# DAM10_Relays.net
KiCad netlist of a schematic drawn in Altium Designer
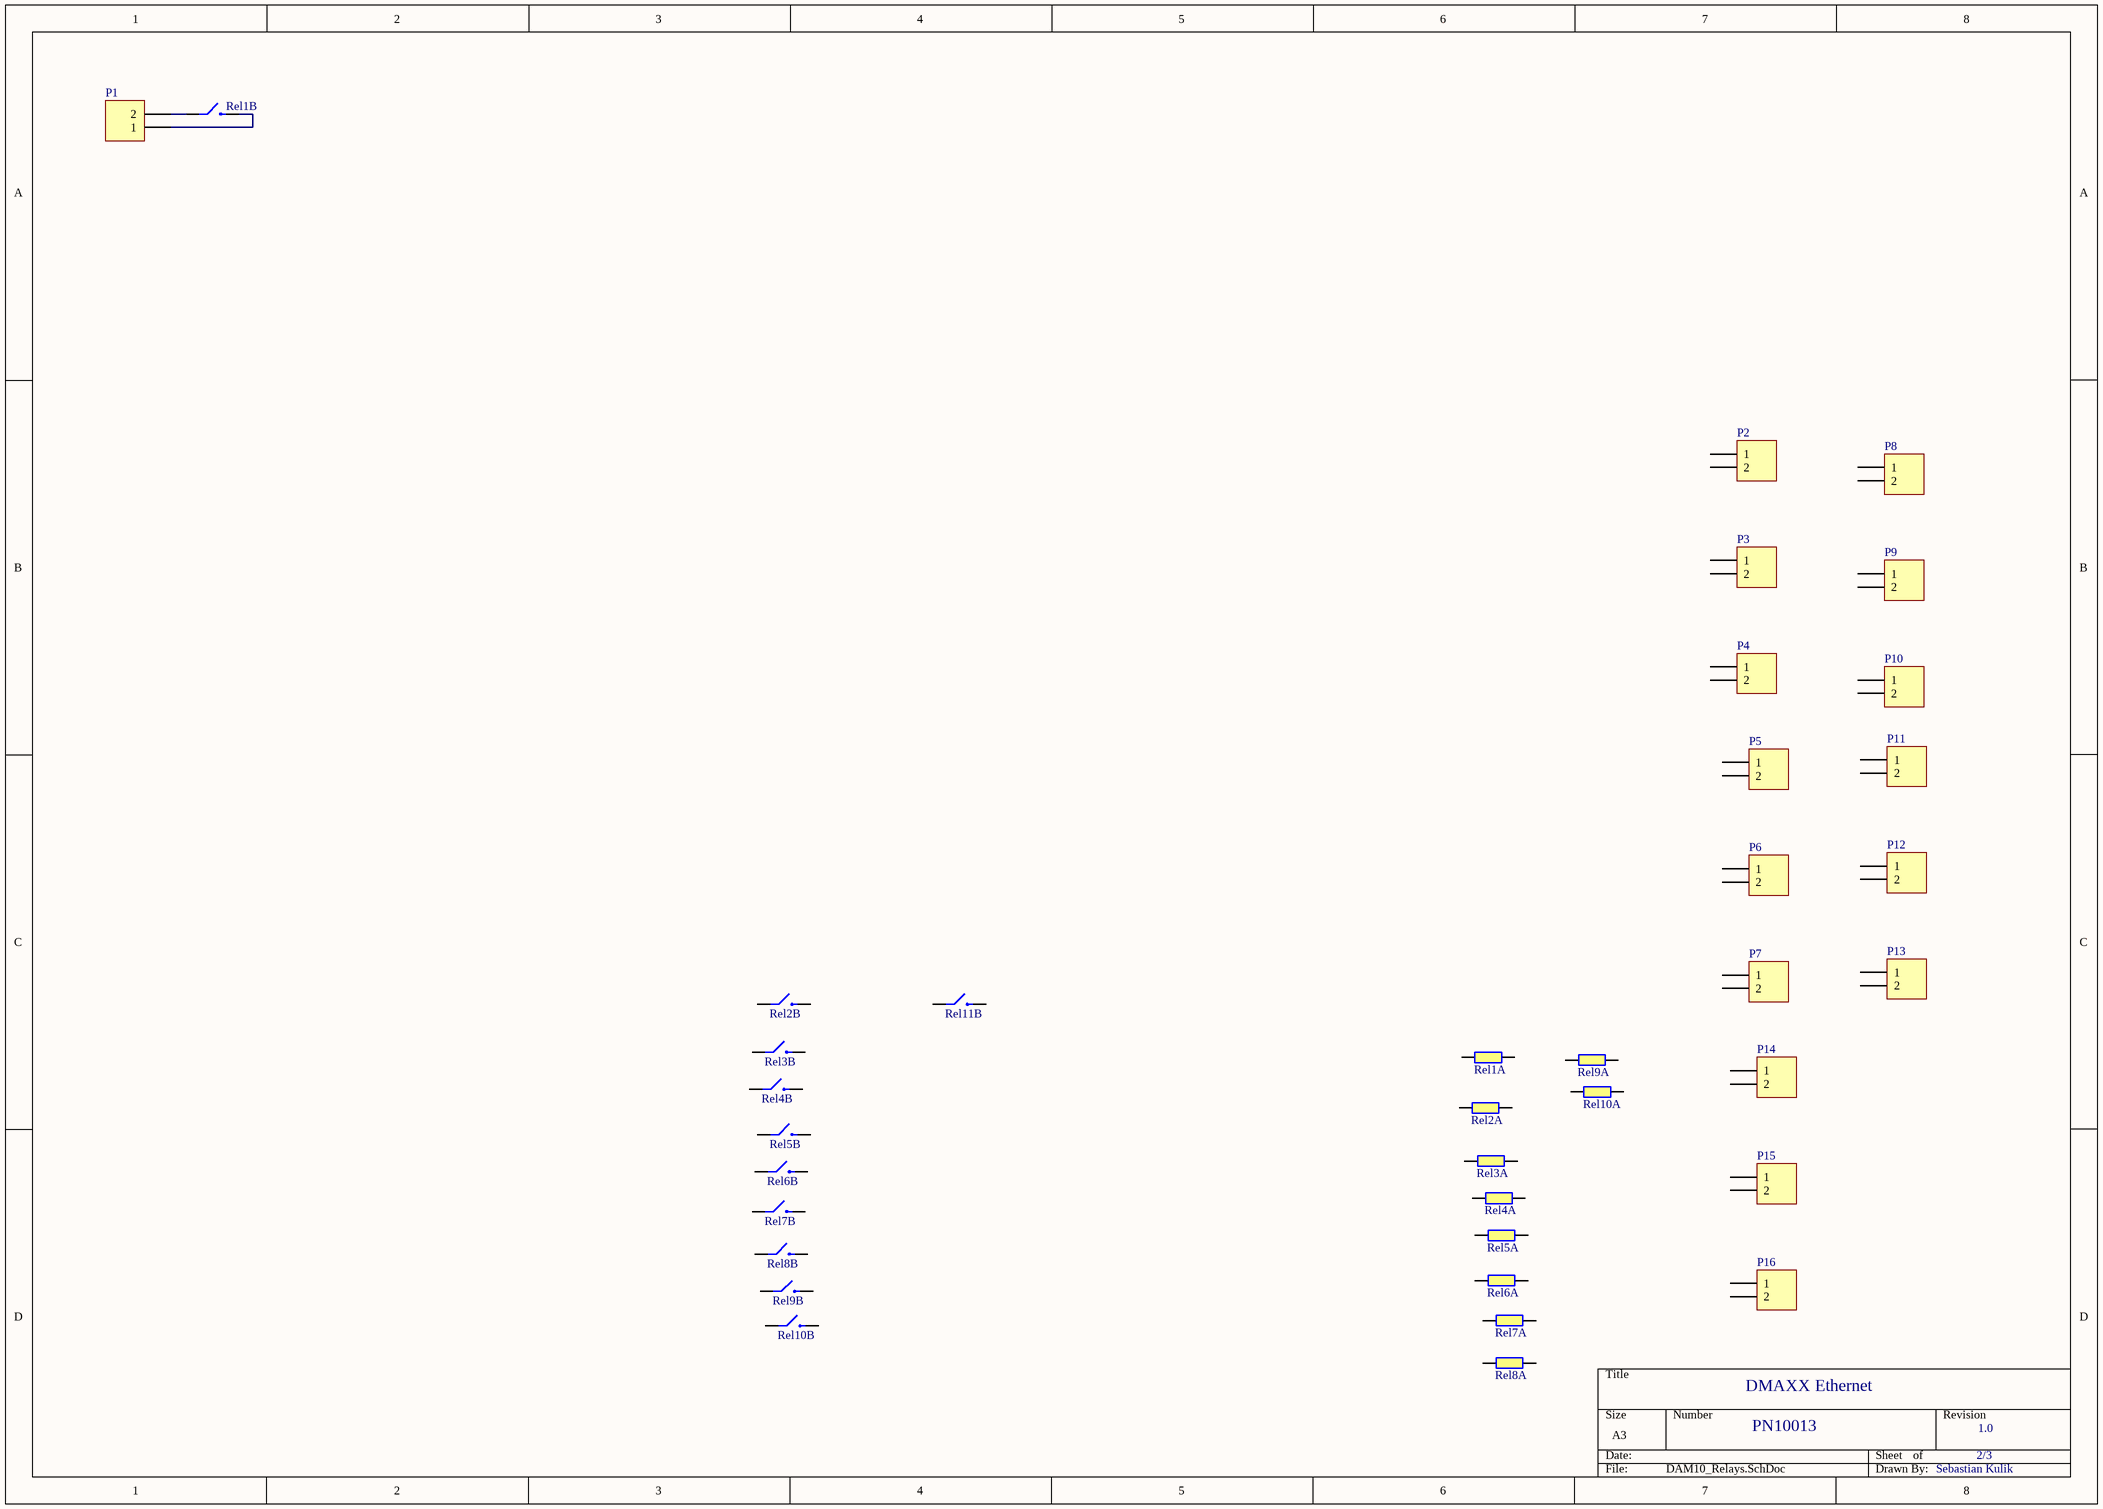
[diagram p0: DAM10_Relays.SchDoc]

(export (version "E")
  (design (tool "Eeschema 10.0.6"))
  (components
    (comp (ref "P1")
      (value "PHOENIX_1715721")
      (footprint "Phoenix-2-5_08")
      (description "Phoenix, 2 pol, 5.08mm, 22A, 715721")
      (fields (field (name "MANUFACTURER") "Phoenix") (field (name "PUBLISHER") "Sebastian Kulik"))
      (libsource (lib "") (part "2Pol_1715721_1"))
    )
    (comp (ref "P2")
      (value "PHOENIX_1715721")
      (footprint "Phoenix-2-5_08")
      (description "Phoenix, 2 pol, 5.08mm, 22A, 715721")
      (fields (field (name "MANUFACTURER") "Phoenix") (field (name "PUBLISHER") "Sebastian Kulik"))
      (libsource (lib "Connectors") (part "2Pol_1715721"))
    )
    (comp (ref "P3")
      (value "PHOENIX_1715721")
      (footprint "Phoenix-2-5_08")
      (description "Phoenix, 2 pol, 5.08mm, 22A, 715721")
      (fields (field (name "MANUFACTURER") "Phoenix") (field (name "PUBLISHER") "Sebastian Kulik"))
      (libsource (lib "Connectors") (part "2Pol_1715721"))
    )
    (comp (ref "P4")
      (value "PHOENIX_1715721")
      (footprint "Phoenix-2-5_08")
      (description "Phoenix, 2 pol, 5.08mm, 22A, 715721")
      (fields (field (name "MANUFACTURER") "Phoenix") (field (name "PUBLISHER") "Sebastian Kulik"))
      (libsource (lib "Connectors") (part "2Pol_1715721"))
    )
    (comp (ref "P5")
      (value "PHOENIX_1715721")
      (footprint "Phoenix-2-5_08")
      (description "Phoenix, 2 pol, 5.08mm, 22A, 715721")
      (fields (field (name "MANUFACTURER") "Phoenix") (field (name "PUBLISHER") "Sebastian Kulik"))
      (libsource (lib "Connectors") (part "2Pol_1715721"))
    )
    (comp (ref "P6")
      (value "PHOENIX_1715721")
      (footprint "Phoenix-2-5_08")
      (description "Phoenix, 2 pol, 5.08mm, 22A, 715721")
      (fields (field (name "MANUFACTURER") "Phoenix") (field (name "PUBLISHER") "Sebastian Kulik"))
      (libsource (lib "Connectors") (part "2Pol_1715721"))
    )
    (comp (ref "P7")
      (value "PHOENIX_1715721")
      (footprint "Phoenix-2-5_08")
      (description "Phoenix, 2 pol, 5.08mm, 22A, 715721")
      (fields (field (name "MANUFACTURER") "Phoenix") (field (name "PUBLISHER") "Sebastian Kulik"))
      (libsource (lib "Connectors") (part "2Pol_1715721"))
    )
    (comp (ref "P8")
      (value "PHOENIX_1715721")
      (footprint "Phoenix-2-5_08")
      (description "Phoenix, 2 pol, 5.08mm, 22A, 715721")
      (fields (field (name "MANUFACTURER") "Phoenix") (field (name "PUBLISHER") "Sebastian Kulik"))
      (libsource (lib "Connectors") (part "2Pol_1715721"))
    )
    (comp (ref "P9")
      (value "PHOENIX_1715721")
      (footprint "Phoenix-2-5_08")
      (description "Phoenix, 2 pol, 5.08mm, 22A, 715721")
      (fields (field (name "MANUFACTURER") "Phoenix") (field (name "PUBLISHER") "Sebastian Kulik"))
      (libsource (lib "Connectors") (part "2Pol_1715721"))
    )
    (comp (ref "P10")
      (value "PHOENIX_1715721")
      (footprint "Phoenix-2-5_08")
      (description "Phoenix, 2 pol, 5.08mm, 22A, 715721")
      (fields (field (name "MANUFACTURER") "Phoenix") (field (name "PUBLISHER") "Sebastian Kulik"))
      (libsource (lib "Connectors") (part "2Pol_1715721"))
    )
    (comp (ref "P11")
      (value "PHOENIX_1715721")
      (footprint "Phoenix-2-5_08")
      (description "Phoenix, 2 pol, 5.08mm, 22A, 715721")
      (fields (field (name "MANUFACTURER") "Phoenix") (field (name "PUBLISHER") "Sebastian Kulik"))
      (libsource (lib "Connectors") (part "2Pol_1715721"))
    )
    (comp (ref "P12")
      (value "PHOENIX_1715721")
      (footprint "Phoenix-2-5_08")
      (description "Phoenix, 2 pol, 5.08mm, 22A, 715721")
      (fields (field (name "MANUFACTURER") "Phoenix") (field (name "PUBLISHER") "Sebastian Kulik"))
      (libsource (lib "Connectors") (part "2Pol_1715721"))
    )
    (comp (ref "P13")
      (value "PHOENIX_1715721")
      (footprint "Phoenix-2-5_08")
      (description "Phoenix, 2 pol, 5.08mm, 22A, 715721")
      (fields (field (name "MANUFACTURER") "Phoenix") (field (name "PUBLISHER") "Sebastian Kulik"))
      (libsource (lib "Connectors") (part "2Pol_1715721"))
    )
    (comp (ref "P14")
      (value "PHOENIX_1715721")
      (footprint "Phoenix-2-5_08")
      (description "Phoenix, 2 pol, 5.08mm, 22A, 715721")
      (fields (field (name "MANUFACTURER") "Phoenix") (field (name "PUBLISHER") "Sebastian Kulik"))
      (libsource (lib "Connectors") (part "2Pol_1715721"))
    )
    (comp (ref "P15")
      (value "PHOENIX_1715721")
      (footprint "Phoenix-2-5_08")
      (description "Phoenix, 2 pol, 5.08mm, 22A, 715721")
      (fields (field (name "MANUFACTURER") "Phoenix") (field (name "PUBLISHER") "Sebastian Kulik"))
      (libsource (lib "Connectors") (part "2Pol_1715721"))
    )
    (comp (ref "P16")
      (value "PHOENIX_1715721")
      (footprint "Phoenix-2-5_08")
      (description "Phoenix, 2 pol, 5.08mm, 22A, 715721")
      (fields (field (name "MANUFACTURER") "Phoenix") (field (name "PUBLISHER") "Sebastian Kulik"))
      (libsource (lib "Connectors") (part "2Pol_1715721"))
    )
    (comp (ref "Rel1")
      (value "Finder-43_41-Rel")
      (footprint "Finder-43_41 series")
      (description "Finder-43-Relay, 16A, 12V, 400mW")
      (fields (field (name "MANUFACTURER") "Finder") (field (name "PUBLISHER") "Sebastian Kulik"))
      (libsource (lib "Mechanical") (part "Finder-43_41-Rel"))
    )
    (comp (ref "Rel2")
      (value "Finder-43_41-Rel")
      (footprint "Finder-43_41 series")
      (description "Finder-43-Relay, 16A, 12V, 400mW")
      (fields (field (name "MANUFACTURER") "Finder") (field (name "PUBLISHER") "Sebastian Kulik"))
      (libsource (lib "Mechanical") (part "Finder-43_41-Rel"))
    )
    (comp (ref "Rel3")
      (value "Finder-43_41-Rel")
      (footprint "Finder-43_41 series")
      (description "Finder-43-Relay, 16A, 12V, 400mW")
      (fields (field (name "MANUFACTURER") "Finder") (field (name "PUBLISHER") "Sebastian Kulik"))
      (libsource (lib "Mechanical") (part "Finder-43_41-Rel"))
    )
    (comp (ref "Rel4")
      (value "Finder-43_41-Rel")
      (footprint "Finder-43_41 series")
      (description "Finder-43-Relay, 16A, 12V, 400mW")
      (fields (field (name "MANUFACTURER") "Finder") (field (name "PUBLISHER") "Sebastian Kulik"))
      (libsource (lib "Mechanical") (part "Finder-43_41-Rel"))
    )
    (comp (ref "Rel5")
      (value "Finder-43_41-Rel")
      (footprint "Finder-43_41 series")
      (description "Finder-43-Relay, 16A, 12V, 400mW")
      (fields (field (name "MANUFACTURER") "Finder") (field (name "PUBLISHER") "Sebastian Kulik"))
      (libsource (lib "Mechanical") (part "Finder-43_41-Rel"))
    )
    (comp (ref "Rel6")
      (value "Finder-43_41-Rel")
      (footprint "Finder-43_41 series")
      (description "Finder-43-Relay, 16A, 12V, 400mW")
      (fields (field (name "MANUFACTURER") "Finder") (field (name "PUBLISHER") "Sebastian Kulik"))
      (libsource (lib "Mechanical") (part "Finder-43_41-Rel"))
    )
    (comp (ref "Rel7")
      (value "Finder-43_41-Rel")
      (footprint "Finder-43_41 series")
      (description "Finder-43-Relay, 16A, 12V, 400mW")
      (fields (field (name "MANUFACTURER") "Finder") (field (name "PUBLISHER") "Sebastian Kulik"))
      (libsource (lib "Mechanical") (part "Finder-43_41-Rel"))
    )
    (comp (ref "Rel8")
      (value "Finder-43_41-Rel")
      (footprint "Finder-43_41 series")
      (description "Finder-43-Relay, 16A, 12V, 400mW")
      (fields (field (name "MANUFACTURER") "Finder") (field (name "PUBLISHER") "Sebastian Kulik"))
      (libsource (lib "Mechanical") (part "Finder-43_41-Rel"))
    )
    (comp (ref "Rel9")
      (value "Finder-43_41-Rel")
      (footprint "Finder-43_41 series")
      (description "Finder-43-Relay, 16A, 12V, 400mW")
      (fields (field (name "MANUFACTURER") "Finder") (field (name "PUBLISHER") "Sebastian Kulik"))
      (libsource (lib "Mechanical") (part "Finder-43_41-Rel"))
    )
    (comp (ref "Rel10")
      (value "Finder-43_41-Rel")
      (footprint "Finder-43_41 series")
      (description "Finder-43-Relay, 16A, 12V, 400mW")
      (fields (field (name "MANUFACTURER") "Finder") (field (name "PUBLISHER") "Sebastian Kulik"))
      (libsource (lib "Mechanical") (part "Finder-43_41-Rel"))
    )
    (comp (ref "Rel11")
      (value "Finder-43_41-Rel")
      (footprint "Finder-43_41 series")
      (description "Finder-43-Relay, 16A, 12V, 400mW")
      (fields (field (name "MANUFACTURER") "Finder") (field (name "PUBLISHER") "Sebastian Kulik"))
      (libsource (lib "Mechanical") (part "Finder-43_41-Rel"))
    )
  )
  (nets
    (net (code "1") (name "Net-(P1-Pad1)") (class "Default")
      (node (ref "P1") (pin "1") (pinfunction "1_1") (pintype "passive"))
      (node (ref "Rel1") (pin "4") (pinfunction "4_4") (pintype "passive"))
    )
    (net (code "2") (name "Net-(P1-Pad2)") (class "Default")
      (node (ref "P1") (pin "2") (pinfunction "2_2") (pintype "passive"))
      (node (ref "Rel1") (pin "3") (pinfunction "3_3") (pintype "passive"))
    )
    (net (code "3") (name "unconnected-(P2-Pad1)") (class "Default")
      (node (ref "P2") (pin "1") (pinfunction "1_1") (pintype "passive"))
    )
    (net (code "4") (name "unconnected-(P2-Pad2)") (class "Default")
      (node (ref "P2") (pin "2") (pinfunction "2_2") (pintype "passive"))
    )
    (net (code "5") (name "unconnected-(P3-Pad1)") (class "Default")
      (node (ref "P3") (pin "1") (pinfunction "1_1") (pintype "passive"))
    )
    (net (code "6") (name "unconnected-(P3-Pad2)") (class "Default")
      (node (ref "P3") (pin "2") (pinfunction "2_2") (pintype "passive"))
    )
    (net (code "7") (name "unconnected-(P4-Pad1)") (class "Default")
      (node (ref "P4") (pin "1") (pinfunction "1_1") (pintype "passive"))
    )
    (net (code "8") (name "unconnected-(P4-Pad2)") (class "Default")
      (node (ref "P4") (pin "2") (pinfunction "2_2") (pintype "passive"))
    )
    (net (code "9") (name "unconnected-(P5-Pad1)") (class "Default")
      (node (ref "P5") (pin "1") (pinfunction "1_1") (pintype "passive"))
    )
    (net (code "10") (name "unconnected-(P5-Pad2)") (class "Default")
      (node (ref "P5") (pin "2") (pinfunction "2_2") (pintype "passive"))
    )
    (net (code "11") (name "unconnected-(P6-Pad1)") (class "Default")
      (node (ref "P6") (pin "1") (pinfunction "1_1") (pintype "passive"))
    )
    (net (code "12") (name "unconnected-(P6-Pad2)") (class "Default")
      (node (ref "P6") (pin "2") (pinfunction "2_2") (pintype "passive"))
    )
    (net (code "13") (name "unconnected-(P7-Pad1)") (class "Default")
      (node (ref "P7") (pin "1") (pinfunction "1_1") (pintype "passive"))
    )
    (net (code "14") (name "unconnected-(P7-Pad2)") (class "Default")
      (node (ref "P7") (pin "2") (pinfunction "2_2") (pintype "passive"))
    )
    (net (code "15") (name "unconnected-(P8-Pad1)") (class "Default")
      (node (ref "P8") (pin "1") (pinfunction "1_1") (pintype "passive"))
    )
    (net (code "16") (name "unconnected-(P8-Pad2)") (class "Default")
      (node (ref "P8") (pin "2") (pinfunction "2_2") (pintype "passive"))
    )
    (net (code "17") (name "unconnected-(P9-Pad1)") (class "Default")
      (node (ref "P9") (pin "1") (pinfunction "1_1") (pintype "passive"))
    )
    (net (code "18") (name "unconnected-(P9-Pad2)") (class "Default")
      (node (ref "P9") (pin "2") (pinfunction "2_2") (pintype "passive"))
    )
    (net (code "19") (name "unconnected-(P10-Pad1)") (class "Default")
      (node (ref "P10") (pin "1") (pinfunction "1_1") (pintype "passive"))
    )
    (net (code "20") (name "unconnected-(P10-Pad2)") (class "Default")
      (node (ref "P10") (pin "2") (pinfunction "2_2") (pintype "passive"))
    )
    (net (code "21") (name "unconnected-(P11-Pad1)") (class "Default")
      (node (ref "P11") (pin "1") (pinfunction "1_1") (pintype "passive"))
    )
    (net (code "22") (name "unconnected-(P11-Pad2)") (class "Default")
      (node (ref "P11") (pin "2") (pinfunction "2_2") (pintype "passive"))
    )
    (net (code "23") (name "unconnected-(P12-Pad1)") (class "Default")
      (node (ref "P12") (pin "1") (pinfunction "1_1") (pintype "passive"))
    )
    (net (code "24") (name "unconnected-(P12-Pad2)") (class "Default")
      (node (ref "P12") (pin "2") (pinfunction "2_2") (pintype "passive"))
    )
    (net (code "25") (name "unconnected-(P13-Pad1)") (class "Default")
      (node (ref "P13") (pin "1") (pinfunction "1_1") (pintype "passive"))
    )
    (net (code "26") (name "unconnected-(P13-Pad2)") (class "Default")
      (node (ref "P13") (pin "2") (pinfunction "2_2") (pintype "passive"))
    )
    (net (code "27") (name "unconnected-(P14-Pad1)") (class "Default")
      (node (ref "P14") (pin "1") (pinfunction "1_1") (pintype "passive"))
    )
    (net (code "28") (name "unconnected-(P14-Pad2)") (class "Default")
      (node (ref "P14") (pin "2") (pinfunction "2_2") (pintype "passive"))
    )
    (net (code "29") (name "unconnected-(P15-Pad1)") (class "Default")
      (node (ref "P15") (pin "1") (pinfunction "1_1") (pintype "passive"))
    )
    (net (code "30") (name "unconnected-(P15-Pad2)") (class "Default")
      (node (ref "P15") (pin "2") (pinfunction "2_2") (pintype "passive"))
    )
    (net (code "31") (name "unconnected-(P16-Pad1)") (class "Default")
      (node (ref "P16") (pin "1") (pinfunction "1_1") (pintype "passive"))
    )
    (net (code "32") (name "unconnected-(P16-Pad2)") (class "Default")
      (node (ref "P16") (pin "2") (pinfunction "2_2") (pintype "passive"))
    )
    (net (code "33") (name "unconnected-(Rel1-Pad1)") (class "Default")
      (node (ref "Rel1") (pin "1") (pinfunction "1_1") (pintype "passive"))
    )
    (net (code "34") (name "unconnected-(Rel1-Pad2)") (class "Default")
      (node (ref "Rel1") (pin "2") (pinfunction "2_2") (pintype "passive"))
    )
    (net (code "35") (name "unconnected-(Rel2-Pad1)") (class "Default")
      (node (ref "Rel2") (pin "1") (pinfunction "1_1") (pintype "passive"))
    )
    (net (code "36") (name "unconnected-(Rel2-Pad2)") (class "Default")
      (node (ref "Rel2") (pin "2") (pinfunction "2_2") (pintype "passive"))
    )
    (net (code "37") (name "unconnected-(Rel2-Pad3)") (class "Default")
      (node (ref "Rel2") (pin "3") (pinfunction "3_3") (pintype "passive"))
    )
    (net (code "38") (name "unconnected-(Rel2-Pad4)") (class "Default")
      (node (ref "Rel2") (pin "4") (pinfunction "4_4") (pintype "passive"))
    )
    (net (code "39") (name "unconnected-(Rel3-Pad1)") (class "Default")
      (node (ref "Rel3") (pin "1") (pinfunction "1_1") (pintype "passive"))
    )
    (net (code "40") (name "unconnected-(Rel3-Pad2)") (class "Default")
      (node (ref "Rel3") (pin "2") (pinfunction "2_2") (pintype "passive"))
    )
    (net (code "41") (name "unconnected-(Rel3-Pad3)") (class "Default")
      (node (ref "Rel3") (pin "3") (pinfunction "3_3") (pintype "passive"))
    )
    (net (code "42") (name "unconnected-(Rel3-Pad4)") (class "Default")
      (node (ref "Rel3") (pin "4") (pinfunction "4_4") (pintype "passive"))
    )
    (net (code "43") (name "unconnected-(Rel4-Pad1)") (class "Default")
      (node (ref "Rel4") (pin "1") (pinfunction "1_1") (pintype "passive"))
    )
    (net (code "44") (name "unconnected-(Rel4-Pad2)") (class "Default")
      (node (ref "Rel4") (pin "2") (pinfunction "2_2") (pintype "passive"))
    )
    (net (code "45") (name "unconnected-(Rel4-Pad3)") (class "Default")
      (node (ref "Rel4") (pin "3") (pinfunction "3_3") (pintype "passive"))
    )
    (net (code "46") (name "unconnected-(Rel4-Pad4)") (class "Default")
      (node (ref "Rel4") (pin "4") (pinfunction "4_4") (pintype "passive"))
    )
    (net (code "47") (name "unconnected-(Rel5-Pad1)") (class "Default")
      (node (ref "Rel5") (pin "1") (pinfunction "1_1") (pintype "passive"))
    )
    (net (code "48") (name "unconnected-(Rel5-Pad2)") (class "Default")
      (node (ref "Rel5") (pin "2") (pinfunction "2_2") (pintype "passive"))
    )
    (net (code "49") (name "unconnected-(Rel5-Pad3)") (class "Default")
      (node (ref "Rel5") (pin "3") (pinfunction "3_3") (pintype "passive"))
    )
    (net (code "50") (name "unconnected-(Rel5-Pad4)") (class "Default")
      (node (ref "Rel5") (pin "4") (pinfunction "4_4") (pintype "passive"))
    )
    (net (code "51") (name "unconnected-(Rel6-Pad1)") (class "Default")
      (node (ref "Rel6") (pin "1") (pinfunction "1_1") (pintype "passive"))
    )
    (net (code "52") (name "unconnected-(Rel6-Pad2)") (class "Default")
      (node (ref "Rel6") (pin "2") (pinfunction "2_2") (pintype "passive"))
    )
    (net (code "53") (name "unconnected-(Rel6-Pad3)") (class "Default")
      (node (ref "Rel6") (pin "3") (pinfunction "3_3") (pintype "passive"))
    )
    (net (code "54") (name "unconnected-(Rel6-Pad4)") (class "Default")
      (node (ref "Rel6") (pin "4") (pinfunction "4_4") (pintype "passive"))
    )
    (net (code "55") (name "unconnected-(Rel7-Pad1)") (class "Default")
      (node (ref "Rel7") (pin "1") (pinfunction "1_1") (pintype "passive"))
    )
    (net (code "56") (name "unconnected-(Rel7-Pad2)") (class "Default")
      (node (ref "Rel7") (pin "2") (pinfunction "2_2") (pintype "passive"))
    )
    (net (code "57") (name "unconnected-(Rel7-Pad3)") (class "Default")
      (node (ref "Rel7") (pin "3") (pinfunction "3_3") (pintype "passive"))
    )
    (net (code "58") (name "unconnected-(Rel7-Pad4)") (class "Default")
      (node (ref "Rel7") (pin "4") (pinfunction "4_4") (pintype "passive"))
    )
    (net (code "59") (name "unconnected-(Rel8-Pad1)") (class "Default")
      (node (ref "Rel8") (pin "1") (pinfunction "1_1") (pintype "passive"))
    )
    (net (code "60") (name "unconnected-(Rel8-Pad2)") (class "Default")
      (node (ref "Rel8") (pin "2") (pinfunction "2_2") (pintype "passive"))
    )
    (net (code "61") (name "unconnected-(Rel8-Pad3)") (class "Default")
      (node (ref "Rel8") (pin "3") (pinfunction "3_3") (pintype "passive"))
    )
    (net (code "62") (name "unconnected-(Rel8-Pad4)") (class "Default")
      (node (ref "Rel8") (pin "4") (pinfunction "4_4") (pintype "passive"))
    )
    (net (code "63") (name "unconnected-(Rel9-Pad1)") (class "Default")
      (node (ref "Rel9") (pin "1") (pinfunction "1_1") (pintype "passive"))
    )
    (net (code "64") (name "unconnected-(Rel9-Pad2)") (class "Default")
      (node (ref "Rel9") (pin "2") (pinfunction "2_2") (pintype "passive"))
    )
    (net (code "65") (name "unconnected-(Rel9-Pad3)") (class "Default")
      (node (ref "Rel9") (pin "3") (pinfunction "3_3") (pintype "passive"))
    )
    (net (code "66") (name "unconnected-(Rel9-Pad4)") (class "Default")
      (node (ref "Rel9") (pin "4") (pinfunction "4_4") (pintype "passive"))
    )
    (net (code "67") (name "unconnected-(Rel10-Pad1)") (class "Default")
      (node (ref "Rel10") (pin "1") (pinfunction "1_1") (pintype "passive"))
    )
    (net (code "68") (name "unconnected-(Rel10-Pad2)") (class "Default")
      (node (ref "Rel10") (pin "2") (pinfunction "2_2") (pintype "passive"))
    )
    (net (code "69") (name "unconnected-(Rel10-Pad3)") (class "Default")
      (node (ref "Rel10") (pin "3") (pinfunction "3_3") (pintype "passive"))
    )
    (net (code "70") (name "unconnected-(Rel10-Pad4)") (class "Default")
      (node (ref "Rel10") (pin "4") (pinfunction "4_4") (pintype "passive"))
    )
    (net (code "71") (name "unconnected-(Rel11-Pad3)") (class "Default")
      (node (ref "Rel11") (pin "3") (pinfunction "3_3") (pintype "passive"))
    )
    (net (code "72") (name "unconnected-(Rel11-Pad4)") (class "Default")
      (node (ref "Rel11") (pin "4") (pinfunction "4_4") (pintype "passive"))
    )
  )
)
